# RFH-2.net
KiCad netlist of a schematic drawn in EAGLE
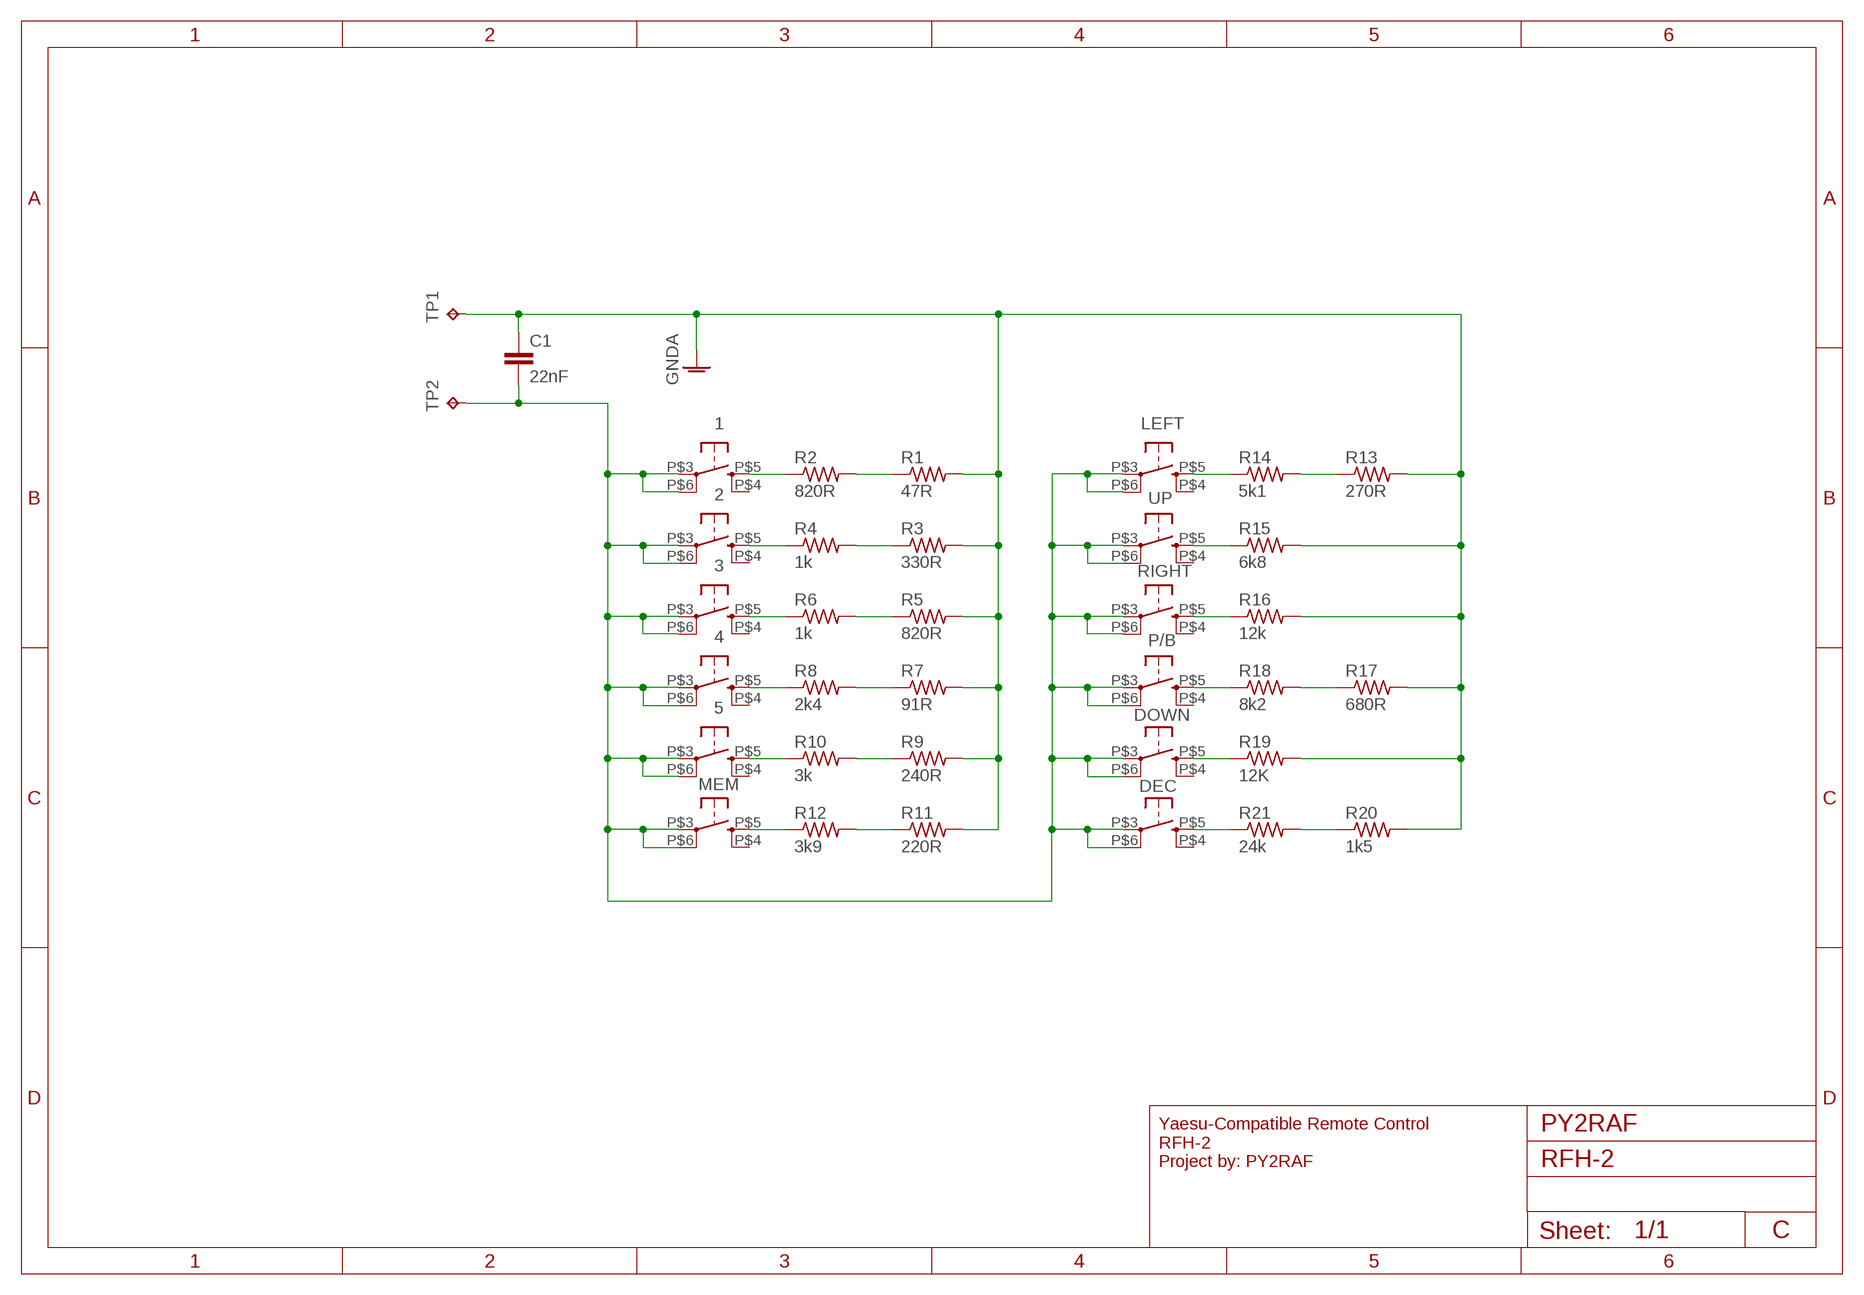
[diagram p0: schematic, sheet 1]

(export (version "E")
  (design (tool "Eeschema 10.0.6"))
  (components
    (comp (ref "1")
      (value "TL6300-SPST")
      (footprint "eagle-import:TL6300")
      (libsource (lib "eagle-import") (part "TL6300-SPST"))
    )
    (comp (ref "2")
      (value "TL6300-SPST")
      (footprint "eagle-import:TL6300")
      (libsource (lib "eagle-import") (part "TL6300-SPST"))
    )
    (comp (ref "3")
      (value "TL6300-SPST")
      (footprint "eagle-import:TL6300")
      (libsource (lib "eagle-import") (part "TL6300-SPST"))
    )
    (comp (ref "4")
      (value "TL6300-SPST")
      (footprint "eagle-import:TL6300")
      (libsource (lib "eagle-import") (part "TL6300-SPST"))
    )
    (comp (ref "5")
      (value "TL6300-SPST")
      (footprint "eagle-import:TL6300")
      (libsource (lib "eagle-import") (part "TL6300-SPST"))
    )
    (comp (ref "C1")
      (value "22nF")
      (footprint "eagle-import:C5B3")
      (libsource (lib "eagle-import") (part "C5/3"))
    )
    (comp (ref "DEC")
      (value "TL6300-SPST")
      (footprint "eagle-import:TL6300")
      (libsource (lib "eagle-import") (part "TL6300-SPST"))
    )
    (comp (ref "DOWN")
      (value "TL6300-SPST")
      (footprint "eagle-import:TL6300")
      (libsource (lib "eagle-import") (part "TL6300-SPST"))
    )
    (comp (ref "LEFT")
      (value "TL6300-SPST")
      (footprint "eagle-import:TL6300")
      (libsource (lib "eagle-import") (part "TL6300-SPST"))
    )
    (comp (ref "MEM")
      (value "TL6300-SPST")
      (footprint "eagle-import:TL6300")
      (libsource (lib "eagle-import") (part "TL6300-SPST"))
    )
    (comp (ref "P/B")
      (value "TL6300-SPST")
      (footprint "eagle-import:TL6300")
      (libsource (lib "eagle-import") (part "TL6300-SPST"))
    )
    (comp (ref "R1")
      (value "47R")
      (footprint "eagle-import:0309_10")
      (libsource (lib "eagle-import") (part "R-US_0309/10"))
    )
    (comp (ref "R2")
      (value "820R")
      (footprint "eagle-import:0309_10")
      (libsource (lib "eagle-import") (part "R-US_0309/10"))
    )
    (comp (ref "R3")
      (value "330R")
      (footprint "eagle-import:0309_10")
      (libsource (lib "eagle-import") (part "R-US_0309/10"))
    )
    (comp (ref "R4")
      (value "1k")
      (footprint "eagle-import:0309_10")
      (libsource (lib "eagle-import") (part "R-US_0309/10"))
    )
    (comp (ref "R5")
      (value "820R")
      (footprint "eagle-import:0309_10")
      (libsource (lib "eagle-import") (part "R-US_0309/10"))
    )
    (comp (ref "R6")
      (value "1k")
      (footprint "eagle-import:0309_10")
      (libsource (lib "eagle-import") (part "R-US_0309/10"))
    )
    (comp (ref "R7")
      (value "91R")
      (footprint "eagle-import:0309_10")
      (libsource (lib "eagle-import") (part "R-US_0309/10"))
    )
    (comp (ref "R8")
      (value "2k4")
      (footprint "eagle-import:0309_10")
      (libsource (lib "eagle-import") (part "R-US_0309/10"))
    )
    (comp (ref "R9")
      (value "240R")
      (footprint "eagle-import:0309_10")
      (libsource (lib "eagle-import") (part "R-US_0309/10"))
    )
    (comp (ref "R10")
      (value "3k")
      (footprint "eagle-import:0309_10")
      (libsource (lib "eagle-import") (part "R-US_0309/10"))
    )
    (comp (ref "R11")
      (value "220R")
      (footprint "eagle-import:0309_10")
      (libsource (lib "eagle-import") (part "R-US_0309/10"))
    )
    (comp (ref "R12")
      (value "3k9")
      (footprint "eagle-import:0309_10")
      (libsource (lib "eagle-import") (part "R-US_0309/10"))
    )
    (comp (ref "R13")
      (value "270R")
      (footprint "eagle-import:0309_10")
      (libsource (lib "eagle-import") (part "R-US_0309/10"))
    )
    (comp (ref "R14")
      (value "5k1")
      (footprint "eagle-import:0309_10")
      (libsource (lib "eagle-import") (part "R-US_0309/10"))
    )
    (comp (ref "R15")
      (value "6k8")
      (footprint "eagle-import:0309_10")
      (libsource (lib "eagle-import") (part "R-US_0309/10"))
    )
    (comp (ref "R16")
      (value "12k")
      (footprint "eagle-import:0309_10")
      (libsource (lib "eagle-import") (part "R-US_0309/10"))
    )
    (comp (ref "R17")
      (value "680R")
      (footprint "eagle-import:0309_10")
      (libsource (lib "eagle-import") (part "R-US_0309/10"))
    )
    (comp (ref "R18")
      (value "8k2")
      (footprint "eagle-import:0309_10")
      (libsource (lib "eagle-import") (part "R-US_0309/10"))
    )
    (comp (ref "R19")
      (value "12K")
      (footprint "eagle-import:0309_10")
      (libsource (lib "eagle-import") (part "R-US_0309/10"))
    )
    (comp (ref "R20")
      (value "1k5")
      (footprint "eagle-import:0309_10")
      (libsource (lib "eagle-import") (part "R-US_0309/10"))
    )
    (comp (ref "R21")
      (value "24k")
      (footprint "eagle-import:0309_10")
      (libsource (lib "eagle-import") (part "R-US_0309/10"))
    )
    (comp (ref "RIGHT")
      (value "TL6300-SPST")
      (footprint "eagle-import:TL6300")
      (libsource (lib "eagle-import") (part "TL6300-SPST"))
    )
    (comp (ref "TP1")
      (value "TPPAD1-20Y")
      (footprint "eagle-import:P1-20Y")
      (libsource (lib "eagle-import") (part "TPPAD1-20Y"))
    )
    (comp (ref "TP2")
      (value "TPPAD1-20Y")
      (footprint "eagle-import:P1-20Y")
      (libsource (lib "eagle-import") (part "TPPAD1-20Y"))
    )
    (comp (ref "UP")
      (value "TL6300-SPST")
      (footprint "eagle-import:TL6300")
      (libsource (lib "eagle-import") (part "TL6300-SPST"))
    )
  )
  (nets
    (net (code "1") (name "GNDA") (class "Default")
      (node (ref "C1") (pin "1") (pinfunction "1_1") (pintype "passive"))
      (node (ref "R1") (pin "2") (pinfunction "2_2") (pintype "passive"))
      (node (ref "R11") (pin "2") (pinfunction "2_2") (pintype "passive"))
      (node (ref "R13") (pin "2") (pinfunction "2_2") (pintype "passive"))
      (node (ref "R15") (pin "2") (pinfunction "2_2") (pintype "passive"))
      (node (ref "R16") (pin "2") (pinfunction "2_2") (pintype "passive"))
      (node (ref "R17") (pin "2") (pinfunction "2_2") (pintype "passive"))
      (node (ref "R19") (pin "2") (pinfunction "2_2") (pintype "passive"))
      (node (ref "R20") (pin "2") (pinfunction "2_2") (pintype "passive"))
      (node (ref "R3") (pin "2") (pinfunction "2_2") (pintype "passive"))
      (node (ref "R5") (pin "2") (pinfunction "2_2") (pintype "passive"))
      (node (ref "R7") (pin "2") (pinfunction "2_2") (pintype "passive"))
      (node (ref "R9") (pin "2") (pinfunction "2_2") (pintype "passive"))
      (node (ref "TP1") (pin "TP") (pinfunction "TP_TP") (pintype "input"))
    )
    (net (code "2") (name "Net-(1-P)") (class "Default")
      (node (ref "1") (pin "P$3") (pinfunction "P_P$3") (pintype "passive"))
      (node (ref "1") (pin "P$6") (pinfunction "P1_P$6") (pintype "passive"))
      (node (ref "2") (pin "P$3") (pinfunction "P_P$3") (pintype "passive"))
      (node (ref "2") (pin "P$6") (pinfunction "P1_P$6") (pintype "passive"))
      (node (ref "3") (pin "P$3") (pinfunction "P_P$3") (pintype "passive"))
      (node (ref "3") (pin "P$6") (pinfunction "P1_P$6") (pintype "passive"))
      (node (ref "4") (pin "P$3") (pinfunction "P_P$3") (pintype "passive"))
      (node (ref "4") (pin "P$6") (pinfunction "P1_P$6") (pintype "passive"))
      (node (ref "5") (pin "P$3") (pinfunction "P_P$3") (pintype "passive"))
      (node (ref "5") (pin "P$6") (pinfunction "P1_P$6") (pintype "passive"))
      (node (ref "C1") (pin "2") (pinfunction "2_2") (pintype "passive"))
      (node (ref "DEC") (pin "P$3") (pinfunction "P_P$3") (pintype "passive"))
      (node (ref "DEC") (pin "P$6") (pinfunction "P1_P$6") (pintype "passive"))
      (node (ref "DOWN") (pin "P$3") (pinfunction "P_P$3") (pintype "passive"))
      (node (ref "DOWN") (pin "P$6") (pinfunction "P1_P$6") (pintype "passive"))
      (node (ref "LEFT") (pin "P$3") (pinfunction "P_P$3") (pintype "passive"))
      (node (ref "LEFT") (pin "P$6") (pinfunction "P1_P$6") (pintype "passive"))
      (node (ref "MEM") (pin "P$3") (pinfunction "P_P$3") (pintype "passive"))
      (node (ref "MEM") (pin "P$6") (pinfunction "P1_P$6") (pintype "passive"))
      (node (ref "P/B") (pin "P$3") (pinfunction "P_P$3") (pintype "passive"))
      (node (ref "P/B") (pin "P$6") (pinfunction "P1_P$6") (pintype "passive"))
      (node (ref "RIGHT") (pin "P$3") (pinfunction "P_P$3") (pintype "passive"))
      (node (ref "RIGHT") (pin "P$6") (pinfunction "P1_P$6") (pintype "passive"))
      (node (ref "TP2") (pin "TP") (pinfunction "TP_TP") (pintype "input"))
      (node (ref "UP") (pin "P$3") (pinfunction "P_P$3") (pintype "passive"))
      (node (ref "UP") (pin "P$6") (pinfunction "P1_P$6") (pintype "passive"))
    )
    (net (code "3") (name "Net-(1-S)") (class "Default")
      (node (ref "1") (pin "P$5") (pinfunction "S_P$5") (pintype "passive"))
      (node (ref "R2") (pin "1") (pinfunction "1_1") (pintype "passive"))
    )
    (net (code "4") (name "Net-(2-S)") (class "Default")
      (node (ref "2") (pin "P$5") (pinfunction "S_P$5") (pintype "passive"))
      (node (ref "R4") (pin "1") (pinfunction "1_1") (pintype "passive"))
    )
    (net (code "5") (name "Net-(3-S)") (class "Default")
      (node (ref "3") (pin "P$5") (pinfunction "S_P$5") (pintype "passive"))
      (node (ref "R6") (pin "1") (pinfunction "1_1") (pintype "passive"))
    )
    (net (code "6") (name "Net-(4-S)") (class "Default")
      (node (ref "4") (pin "P$5") (pinfunction "S_P$5") (pintype "passive"))
      (node (ref "R8") (pin "1") (pinfunction "1_1") (pintype "passive"))
    )
    (net (code "7") (name "Net-(5-S)") (class "Default")
      (node (ref "5") (pin "P$5") (pinfunction "S_P$5") (pintype "passive"))
      (node (ref "R10") (pin "1") (pinfunction "1_1") (pintype "passive"))
    )
    (net (code "8") (name "Net-(DEC-S)") (class "Default")
      (node (ref "DEC") (pin "P$5") (pinfunction "S_P$5") (pintype "passive"))
      (node (ref "R21") (pin "1") (pinfunction "1_1") (pintype "passive"))
    )
    (net (code "9") (name "Net-(DOWN-S)") (class "Default")
      (node (ref "DOWN") (pin "P$5") (pinfunction "S_P$5") (pintype "passive"))
      (node (ref "R19") (pin "1") (pinfunction "1_1") (pintype "passive"))
    )
    (net (code "10") (name "Net-(LEFT-S)") (class "Default")
      (node (ref "LEFT") (pin "P$5") (pinfunction "S_P$5") (pintype "passive"))
      (node (ref "R14") (pin "1") (pinfunction "1_1") (pintype "passive"))
    )
    (net (code "11") (name "Net-(MEM-S)") (class "Default")
      (node (ref "MEM") (pin "P$5") (pinfunction "S_P$5") (pintype "passive"))
      (node (ref "R12") (pin "1") (pinfunction "1_1") (pintype "passive"))
    )
    (net (code "12") (name "Net-(P/B-S)") (class "Default")
      (node (ref "P/B") (pin "P$5") (pinfunction "S_P$5") (pintype "passive"))
      (node (ref "R18") (pin "1") (pinfunction "1_1") (pintype "passive"))
    )
    (net (code "13") (name "Net-(R1-Pad1)") (class "Default")
      (node (ref "R1") (pin "1") (pinfunction "1_1") (pintype "passive"))
      (node (ref "R2") (pin "2") (pinfunction "2_2") (pintype "passive"))
    )
    (net (code "14") (name "Net-(R3-Pad1)") (class "Default")
      (node (ref "R3") (pin "1") (pinfunction "1_1") (pintype "passive"))
      (node (ref "R4") (pin "2") (pinfunction "2_2") (pintype "passive"))
    )
    (net (code "15") (name "Net-(R5-Pad1)") (class "Default")
      (node (ref "R5") (pin "1") (pinfunction "1_1") (pintype "passive"))
      (node (ref "R6") (pin "2") (pinfunction "2_2") (pintype "passive"))
    )
    (net (code "16") (name "Net-(R7-Pad1)") (class "Default")
      (node (ref "R7") (pin "1") (pinfunction "1_1") (pintype "passive"))
      (node (ref "R8") (pin "2") (pinfunction "2_2") (pintype "passive"))
    )
    (net (code "17") (name "Net-(R10-Pad2)") (class "Default")
      (node (ref "R10") (pin "2") (pinfunction "2_2") (pintype "passive"))
      (node (ref "R9") (pin "1") (pinfunction "1_1") (pintype "passive"))
    )
    (net (code "18") (name "Net-(R11-Pad1)") (class "Default")
      (node (ref "R11") (pin "1") (pinfunction "1_1") (pintype "passive"))
      (node (ref "R12") (pin "2") (pinfunction "2_2") (pintype "passive"))
    )
    (net (code "19") (name "Net-(R13-Pad1)") (class "Default")
      (node (ref "R13") (pin "1") (pinfunction "1_1") (pintype "passive"))
      (node (ref "R14") (pin "2") (pinfunction "2_2") (pintype "passive"))
    )
    (net (code "20") (name "Net-(R17-Pad1)") (class "Default")
      (node (ref "R17") (pin "1") (pinfunction "1_1") (pintype "passive"))
      (node (ref "R18") (pin "2") (pinfunction "2_2") (pintype "passive"))
    )
    (net (code "21") (name "Net-(R20-Pad1)") (class "Default")
      (node (ref "R20") (pin "1") (pinfunction "1_1") (pintype "passive"))
      (node (ref "R21") (pin "2") (pinfunction "2_2") (pintype "passive"))
    )
    (net (code "22") (name "Net-(RIGHT-S)") (class "Default")
      (node (ref "R16") (pin "1") (pinfunction "1_1") (pintype "passive"))
      (node (ref "RIGHT") (pin "P$5") (pinfunction "S_P$5") (pintype "passive"))
    )
    (net (code "23") (name "Net-(UP-S)") (class "Default")
      (node (ref "R15") (pin "1") (pinfunction "1_1") (pintype "passive"))
      (node (ref "UP") (pin "P$5") (pinfunction "S_P$5") (pintype "passive"))
    )
    (net (code "24") (name "unconnected-(1-S1-PadP$4)") (class "Default")
      (node (ref "1") (pin "P$4") (pinfunction "S1_P$4") (pintype "passive"))
    )
    (net (code "25") (name "unconnected-(2-S1-PadP$4)") (class "Default")
      (node (ref "2") (pin "P$4") (pinfunction "S1_P$4") (pintype "passive"))
    )
    (net (code "26") (name "unconnected-(3-S1-PadP$4)") (class "Default")
      (node (ref "3") (pin "P$4") (pinfunction "S1_P$4") (pintype "passive"))
    )
    (net (code "27") (name "unconnected-(4-S1-PadP$4)") (class "Default")
      (node (ref "4") (pin "P$4") (pinfunction "S1_P$4") (pintype "passive"))
    )
    (net (code "28") (name "unconnected-(5-S1-PadP$4)") (class "Default")
      (node (ref "5") (pin "P$4") (pinfunction "S1_P$4") (pintype "passive"))
    )
    (net (code "29") (name "unconnected-(DEC-S1-PadP$4)") (class "Default")
      (node (ref "DEC") (pin "P$4") (pinfunction "S1_P$4") (pintype "passive"))
    )
    (net (code "30") (name "unconnected-(DOWN-S1-PadP$4)") (class "Default")
      (node (ref "DOWN") (pin "P$4") (pinfunction "S1_P$4") (pintype "passive"))
    )
    (net (code "31") (name "unconnected-(LEFT-S1-PadP$4)") (class "Default")
      (node (ref "LEFT") (pin "P$4") (pinfunction "S1_P$4") (pintype "passive"))
    )
    (net (code "32") (name "unconnected-(MEM-S1-PadP$4)") (class "Default")
      (node (ref "MEM") (pin "P$4") (pinfunction "S1_P$4") (pintype "passive"))
    )
    (net (code "33") (name "unconnected-(P/B-S1-PadP$4)") (class "Default")
      (node (ref "P/B") (pin "P$4") (pinfunction "S1_P$4") (pintype "passive"))
    )
    (net (code "34") (name "unconnected-(RIGHT-S1-PadP$4)") (class "Default")
      (node (ref "RIGHT") (pin "P$4") (pinfunction "S1_P$4") (pintype "passive"))
    )
    (net (code "35") (name "unconnected-(UP-S1-PadP$4)") (class "Default")
      (node (ref "UP") (pin "P$4") (pinfunction "S1_P$4") (pintype "passive"))
    )
  )
)
